# MCU_CAN.net
KiCad netlist of a schematic drawn in Altium Designer
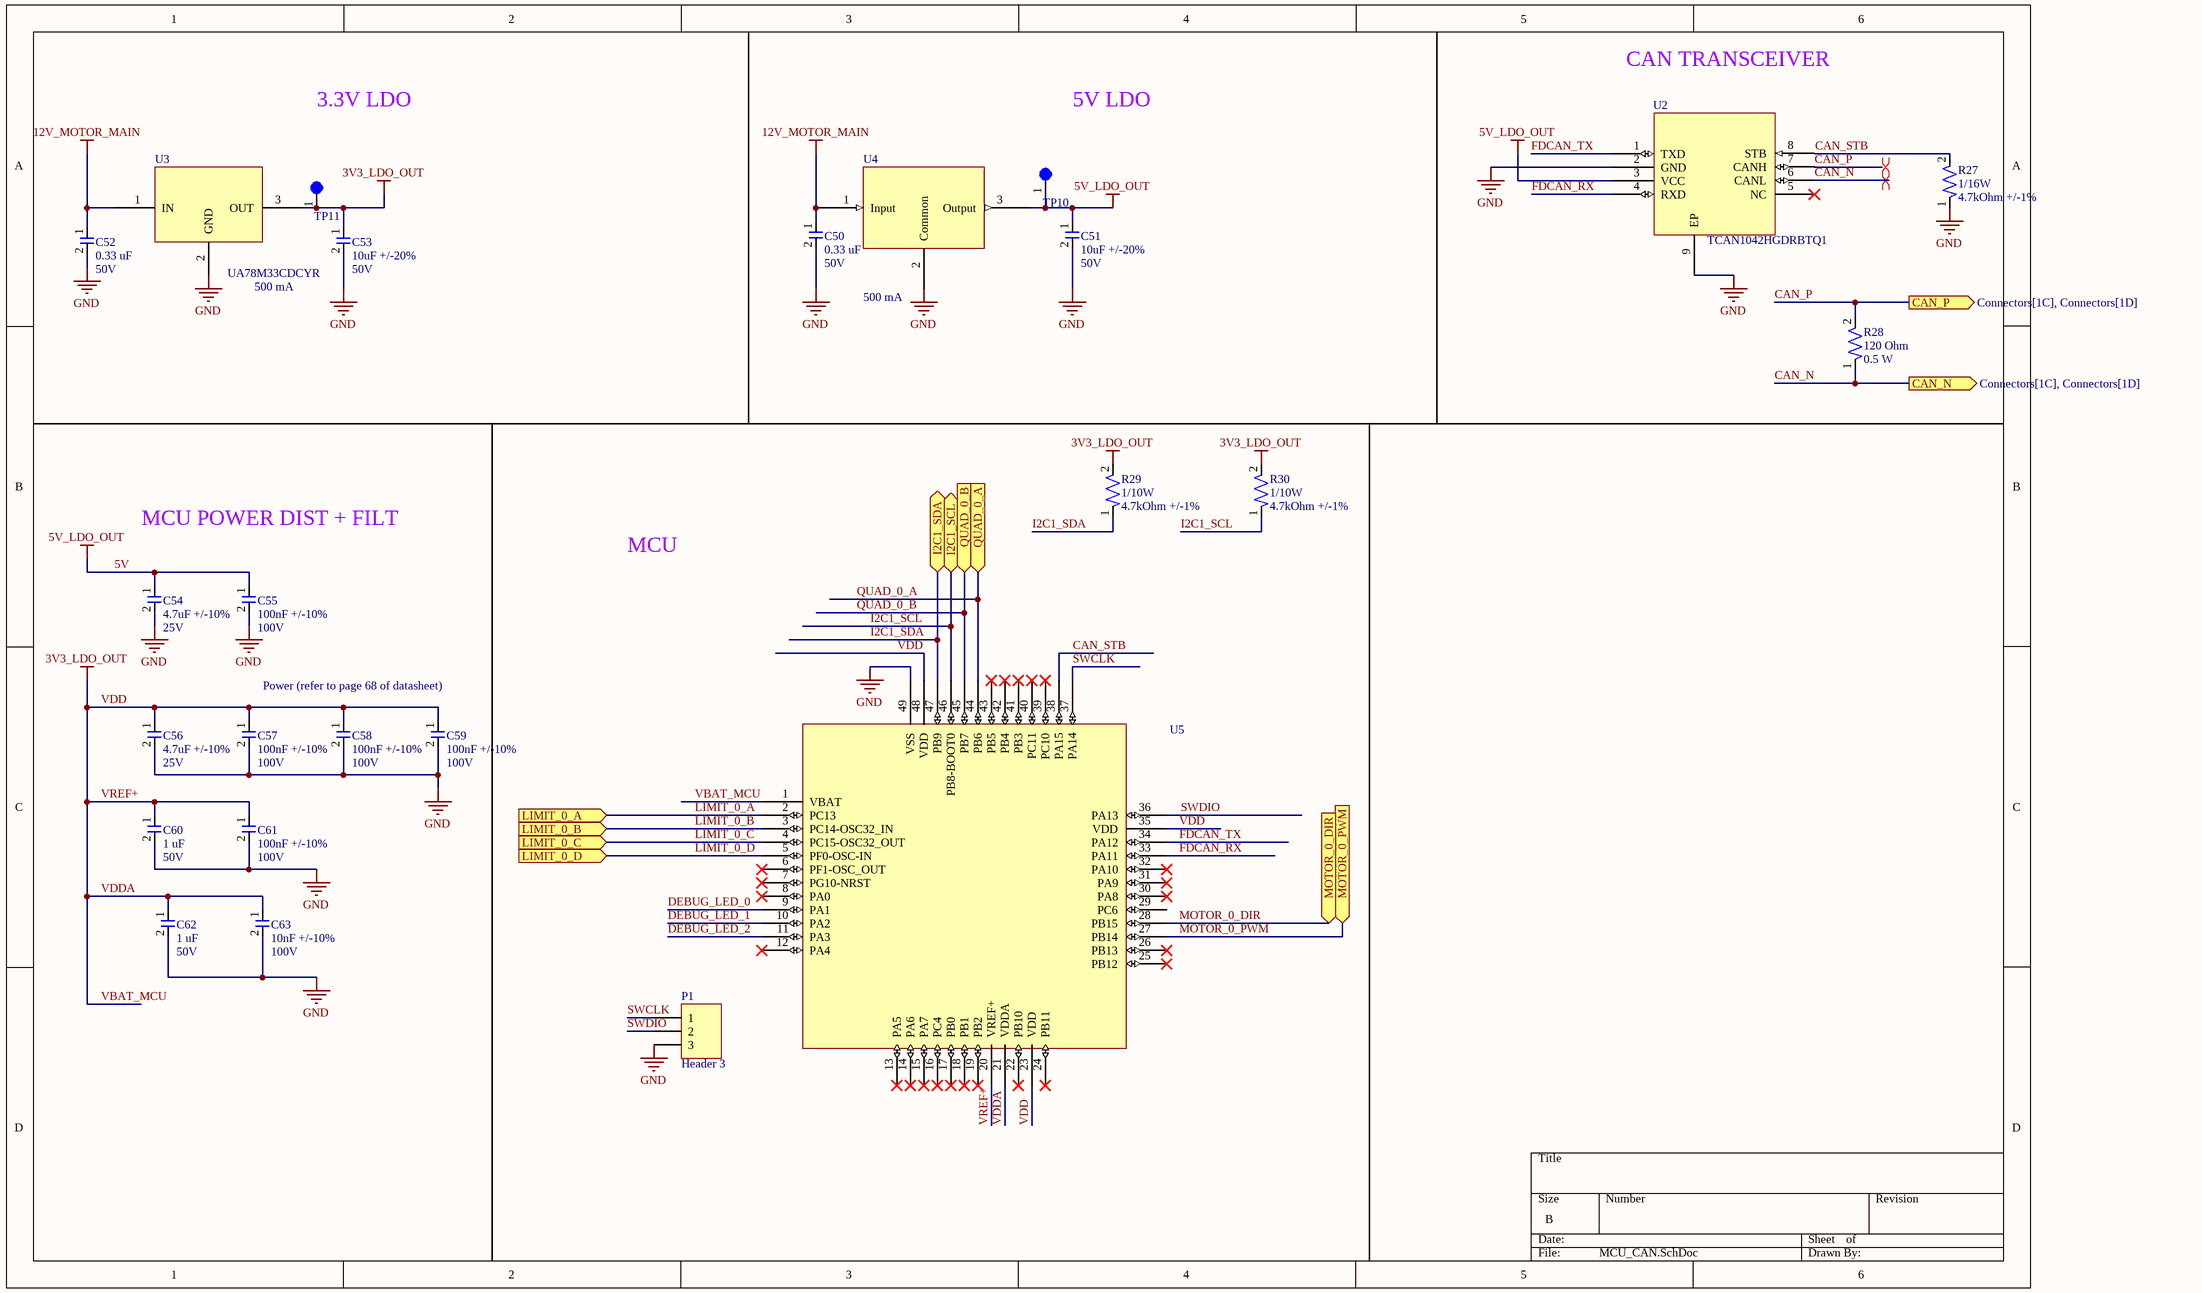
[diagram p0: MCU_CAN.SchDoc]

(export (version "E")
  (design (tool "Eeschema 10.0.6"))
  (components
    (comp (ref "C50")
      (value "CGA3E3X7R1H334K080AB")
      (footprint "CAP-0603")
      (description "0.33 µF ±10% 50V Ceramic Capacitor X7R 0603 (1608 Metric)")
      (fields
        (field (name "MANUFACTURER") "TDK Corporation")
        (field (name "TOLERANCE") "+/- 10%")
        (field (name "CAPACITANCE") "0.33 uF")
        (field (name "VOLTAGE") "50V")
      )
      (libsource (lib "MasterLib") (part "CAP-0.33uF-0001"))
    )
    (comp (ref "C51")
      (value "CL31B106KBHNNNE")
      (footprint "CAP-1206")
      (description "10 µF ±10% 50V Ceramic Capacitor X7R 1206 (3216 Metric)")
      (fields
        (field (name "MANUFACTURER") "Samsung Electro-Mechanics")
        (field (name "CAPACITANCE") "10uF +/-20%")
        (field (name "VOLTAGE RATING") "50V")
      )
      (libsource (lib "MasterLib") (part "CAP-10U-0001"))
    )
    (comp (ref "C52")
      (value "CGA3E3X7R1H334K080AB")
      (footprint "CAP-0603")
      (description "0.33 µF ±10% 50V Ceramic Capacitor X7R 0603 (1608 Metric)")
      (fields
        (field (name "MANUFACTURER") "TDK Corporation")
        (field (name "TOLERANCE") "+/- 10%")
        (field (name "CAPACITANCE") "0.33 uF")
        (field (name "VOLTAGE") "50V")
      )
      (libsource (lib "MasterLib") (part "CAP-0.33uF-0001"))
    )
    (comp (ref "C53")
      (value "CL31B106KBHNNNE")
      (footprint "CAP-1206")
      (description "10 µF ±10% 50V Ceramic Capacitor X7R 1206 (3216 Metric)")
      (fields
        (field (name "MANUFACTURER") "Samsung Electro-Mechanics")
        (field (name "CAPACITANCE") "10uF +/-20%")
        (field (name "VOLTAGE RATING") "50V")
      )
      (libsource (lib "MasterLib") (part "CAP-10U-0001"))
    )
    (comp (ref "C54")
      (value "TMK107BBJ475KA-T")
      (footprint "CAP-0603")
      (description "4.7 µF ±10% 25V Ceramic Capacitor X5R 0603 (1608 Metric)")
      (fields
        (field (name "MANUFACTURER") "Taiyo Yuden")
        (field (name "CAPACITANCE") "4.7uF +/-10%")
        (field (name "VOLTAGE RATING") "25V")
      )
      (libsource (lib "MasterLib") (part "CAP-4.7U-0001"))
    )
    (comp (ref "C55")
      (value "CC0603KRX7R0BB104")
      (footprint "CAP-0603")
      (description "CAP CER 0.1UF 100V X7R 0603")
      (fields
        (field (name "MANUFACTURER") "YAGEO")
        (field (name "CAPACITANCE") "100nF +/-10%")
        (field (name "VOLTAGE RATING") "100V")
      )
      (libsource (lib "MasterLib") (part "CAP-100N-0001"))
    )
    (comp (ref "C56")
      (value "TMK107BBJ475KA-T")
      (footprint "CAP-0603")
      (description "4.7 µF ±10% 25V Ceramic Capacitor X5R 0603 (1608 Metric)")
      (fields
        (field (name "MANUFACTURER") "Taiyo Yuden")
        (field (name "CAPACITANCE") "4.7uF +/-10%")
        (field (name "VOLTAGE RATING") "25V")
      )
      (libsource (lib "MasterLib") (part "CAP-4.7U-0001"))
    )
    (comp (ref "C57")
      (value "CC0603KRX7R0BB104")
      (footprint "CAP-0603")
      (description "CAP CER 0.1UF 100V X7R 0603")
      (fields
        (field (name "MANUFACTURER") "YAGEO")
        (field (name "CAPACITANCE") "100nF +/-10%")
        (field (name "VOLTAGE RATING") "100V")
      )
      (libsource (lib "MasterLib") (part "CAP-100N-0001"))
    )
    (comp (ref "C58")
      (value "CC0603KRX7R0BB104")
      (footprint "CAP-0603")
      (description "CAP CER 0.1UF 100V X7R 0603")
      (fields
        (field (name "MANUFACTURER") "YAGEO")
        (field (name "CAPACITANCE") "100nF +/-10%")
        (field (name "VOLTAGE RATING") "100V")
      )
      (libsource (lib "MasterLib") (part "CAP-100N-0001"))
    )
    (comp (ref "C59")
      (value "CC0603KRX7R0BB104")
      (footprint "CAP-0603")
      (description "CAP CER 0.1UF 100V X7R 0603")
      (fields
        (field (name "MANUFACTURER") "YAGEO")
        (field (name "CAPACITANCE") "100nF +/-10%")
        (field (name "VOLTAGE RATING") "100V")
      )
      (libsource (lib "MasterLib") (part "CAP-100N-0001"))
    )
    (comp (ref "C60")
      (value "UMK107AB7105KA-T")
      (footprint "CAP-0603")
      (description "1 µF ±10% 50V Ceramic Capacitor X7R 0603 (1608 Metric)")
      (fields (field (name "CAPACITANCE") "1 uF") (field (name "VOLTAGE") "50V"))
      (libsource (lib "MasterLib") (part "CAP-1U-0002"))
    )
    (comp (ref "C61")
      (value "CC0603KRX7R0BB104")
      (footprint "CAP-0603")
      (description "CAP CER 0.1UF 100V X7R 0603")
      (fields
        (field (name "MANUFACTURER") "YAGEO")
        (field (name "CAPACITANCE") "100nF +/-10%")
        (field (name "VOLTAGE RATING") "100V")
      )
      (libsource (lib "MasterLib") (part "CAP-100N-0001"))
    )
    (comp (ref "C62")
      (value "UMK107AB7105KA-T")
      (footprint "CAP-0603")
      (description "1 µF ±10% 50V Ceramic Capacitor X7R 0603 (1608 Metric)")
      (fields (field (name "CAPACITANCE") "1 uF") (field (name "VOLTAGE") "50V"))
      (libsource (lib "MasterLib") (part "CAP-1U-0002"))
    )
    (comp (ref "C63")
      (value "CC0402KRX7R0BB103")
      (footprint "CAP-0402")
      (description "10000 pF ±10% 100V Ceramic Capacitor X7R 0402 (1005 Metric)")
      (fields
        (field (name "MANUFACTURER") "YAGEO")
        (field (name "CAPACITANCE") "10nF +/-10%")
        (field (name "VOLTAGE RATING") "100V")
      )
      (libsource (lib "MasterLib") (part "CAP-10N-0001"))
    )
    (comp (ref "P1")
      (value "Header 3")
      (footprint "HDR1X3")
      (description "Header, 3-Pin")
      (fields (field (name "PUBLISHER") "Altium Limited"))
      (libsource (lib "Miscellaneous Connectors") (part "Header 3"))
    )
    (comp (ref "R27")
      (value "RC0402FR-074K7P")
      (footprint "RES-0402")
      (description "RES SMD 4.7K OHM 1% 1/16W 0402")
      (fields
        (field (name "MANUFACTURER") "YAGEO")
        (field (name "POWER RATING") "1/16W")
        (field (name "RESISTANCE") "4.7kOhm +/-1%")
      )
      (libsource (lib "MasterLib") (part "RES-4.7K-0001"))
    )
    (comp (ref "R28")
      (value "CRGH1206F120R")
      (footprint "RES-1206")
      (description "120 Ohms ±1% 0.5W, 1/2W Chip Resistor 1206 (3216 Metric) Thick Film")
      (fields
        (field (name "TOLERANCE") "1%")
        (field (name "RESISTANCE") "120 Ohm")
        (field (name "POWER") "0.5 W")
      )
      (libsource (lib "MasterLib") (part "RES-120-0002"))
    )
    (comp (ref "R29")
      (value "AF0603FR-074K7L")
      (footprint "RES-0603")
      (description "RES SMD 4.7K OHM 1% 1/10W 0603")
      (fields
        (field (name "MANUFACTURER") "YAGEO")
        (field (name "POWER RATING") "1/10W")
        (field (name "RESISTANCE") "4.7kOhm +/-1%")
      )
      (libsource (lib "MasterLib") (part "RES-4.7K-0002"))
    )
    (comp (ref "R30")
      (value "AF0603FR-074K7L")
      (footprint "RES-0603")
      (description "RES SMD 4.7K OHM 1% 1/10W 0603")
      (fields
        (field (name "MANUFACTURER") "YAGEO")
        (field (name "POWER RATING") "1/10W")
        (field (name "RESISTANCE") "4.7kOhm +/-1%")
      )
      (libsource (lib "MasterLib") (part "RES-4.7K-0002"))
    )
    (comp (ref "TP10")
      (value "5003")
      (footprint "TEST-POINT-0001")
      (description "Oranange PC Test Point, Miniature Phoisphor Bronze Silver Plating Through Hole Mounting Type")
      (libsource (lib "MasterLib") (part "TEST-POINT-0001"))
    )
    (comp (ref "TP11")
      (value "5003")
      (footprint "TEST-POINT-0001")
      (description "Oranange PC Test Point, Miniature Phoisphor Bronze Silver Plating Through Hole Mounting Type")
      (libsource (lib "MasterLib") (part "TEST-POINT-0001"))
    )
    (comp (ref "U2")
      (value "TCAN1042HGDRBTQ1")
      (footprint "IC-8-VSON")
      (description "1/1 Transceiver CANbus 8-VSON (3x3)")
      (fields (field (name "MANUFACTURER") "Texas Instrument"))
      (libsource (lib "MasterLib") (part "IC-CAN-TRANSCEIVER-0002"))
    )
    (comp (ref "U3")
      (value "UA78M33CDCYR")
      (footprint "IC-SOT-223-4")
      (description "Linear Voltage Regulator IC Positive Fixed 1 Output 500mA SOT-223-4")
      (fields (field (name "CURRENT") "500 mA"))
      (libsource (lib "MasterLib") (part "IC-LDO-3.3V-0002"))
    )
    (comp (ref "U4")
      (value "UA78M05IDCYR")
      (footprint "IC-SOT-223-4")
      (description "Linear Voltage Regulator IC Positive Fixed 1 Output 500mA SOT-223-4")
      (fields (field (name "MANUFACTURER") "Texas Instruments") (field (name "CURRENT") "500 mA"))
      (libsource (lib "MasterLib") (part "IC-LDO-5V-0003"))
    )
    (comp (ref "U5")
      (value "STM32G431CBU6")
      (footprint "MCU-UFQFPN48")
      (libsource (lib "MasterLib") (part "IC-STM32G431CBU6"))
    )
  )
  (nets
    (net (code "1") (name "/CAN_N") (class "Default")
      (node (ref "R28") (pin "1") (pinfunction "1_1") (pintype "passive"))
      (node (ref "U2") (pin "6") (pinfunction "CANL_6") (pintype "bidirectional"))
    )
    (net (code "2") (name "/CAN_P") (class "Default")
      (node (ref "R28") (pin "2") (pinfunction "2_2") (pintype "passive"))
      (node (ref "U2") (pin "7") (pinfunction "CANH_7") (pintype "bidirectional"))
    )
    (net (code "3") (name "/CAN_STB") (class "Default")
      (node (ref "R27") (pin "2") (pinfunction "2_2") (pintype "passive"))
      (node (ref "U2") (pin "8") (pinfunction "STB_8") (pintype "input"))
      (node (ref "U5") (pin "38") (pinfunction "PA15_38") (pintype "bidirectional"))
    )
    (net (code "4") (name "/DEBUG_LED_0") (class "Default")
      (node (ref "U5") (pin "9") (pinfunction "PA1_9") (pintype "bidirectional"))
    )
    (net (code "5") (name "/DEBUG_LED_1") (class "Default")
      (node (ref "U5") (pin "10") (pinfunction "PA2_10") (pintype "bidirectional"))
    )
    (net (code "6") (name "/DEBUG_LED_2") (class "Default")
      (node (ref "U5") (pin "11") (pinfunction "PA3_11") (pintype "bidirectional"))
    )
    (net (code "7") (name "/FDCAN_RX") (class "Default")
      (node (ref "U2") (pin "4") (pinfunction "RXD_4") (pintype "bidirectional"))
      (node (ref "U5") (pin "33") (pinfunction "PA11_33") (pintype "bidirectional"))
    )
    (net (code "8") (name "/FDCAN_TX") (class "Default")
      (node (ref "U2") (pin "1") (pinfunction "TXD_1") (pintype "bidirectional"))
      (node (ref "U5") (pin "34") (pinfunction "PA12_34") (pintype "bidirectional"))
    )
    (net (code "9") (name "/I2C1_SCL") (class "Default")
      (node (ref "R30") (pin "1") (pinfunction "1_1") (pintype "passive"))
      (node (ref "U5") (pin "46") (pinfunction "PB8-BOOT0_46") (pintype "bidirectional"))
    )
    (net (code "10") (name "/I2C1_SDA") (class "Default")
      (node (ref "R29") (pin "1") (pinfunction "1_1") (pintype "passive"))
      (node (ref "U5") (pin "47") (pinfunction "PB9_47") (pintype "bidirectional"))
    )
    (net (code "11") (name "/LIMIT_0_A") (class "Default")
      (node (ref "U5") (pin "2") (pinfunction "PC13_2") (pintype "bidirectional"))
    )
    (net (code "12") (name "/LIMIT_0_B") (class "Default")
      (node (ref "U5") (pin "3") (pinfunction "PC14-OSC32_IN_3") (pintype "bidirectional"))
    )
    (net (code "13") (name "/LIMIT_0_C") (class "Default")
      (node (ref "U5") (pin "4") (pinfunction "PC15-OSC32_OUT_4") (pintype "bidirectional"))
    )
    (net (code "14") (name "/LIMIT_0_D") (class "Default")
      (node (ref "U5") (pin "5") (pinfunction "PF0-OSC-IN_5") (pintype "bidirectional"))
    )
    (net (code "15") (name "/MOTOR_0_DIR") (class "Default")
      (node (ref "U5") (pin "28") (pinfunction "PB15_28") (pintype "bidirectional"))
    )
    (net (code "16") (name "/MOTOR_0_PWM") (class "Default")
      (node (ref "U5") (pin "27") (pinfunction "PB14_27") (pintype "bidirectional"))
    )
    (net (code "17") (name "/QUAD_0_A") (class "Default")
      (node (ref "U5") (pin "44") (pinfunction "PB6_44") (pintype "bidirectional"))
    )
    (net (code "18") (name "/QUAD_0_B") (class "Default")
      (node (ref "U5") (pin "45") (pinfunction "PB7_45") (pintype "bidirectional"))
    )
    (net (code "19") (name "/SWCLK") (class "Default")
      (node (ref "P1") (pin "1") (pinfunction "1_1") (pintype "passive"))
      (node (ref "U5") (pin "37") (pinfunction "PA14_37") (pintype "bidirectional"))
    )
    (net (code "20") (name "/SWDIO") (class "Default")
      (node (ref "P1") (pin "2") (pinfunction "2_2") (pintype "passive"))
      (node (ref "U5") (pin "36") (pinfunction "PA13_36") (pintype "bidirectional"))
    )
    (net (code "21") (name "3V3_LDO_OUT") (class "Default")
      (node (ref "C53") (pin "1") (pinfunction "1_1") (pintype "passive"))
      (node (ref "C56") (pin "1") (pinfunction "1_1") (pintype "passive"))
      (node (ref "C57") (pin "1") (pinfunction "1_1") (pintype "passive"))
      (node (ref "C58") (pin "1") (pinfunction "1_1") (pintype "passive"))
      (node (ref "C59") (pin "1") (pinfunction "1_1") (pintype "passive"))
      (node (ref "C60") (pin "1") (pinfunction "1_1") (pintype "passive"))
      (node (ref "C61") (pin "1") (pinfunction "1_1") (pintype "passive"))
      (node (ref "C62") (pin "1") (pinfunction "1_1") (pintype "passive"))
      (node (ref "C63") (pin "1") (pinfunction "1_1") (pintype "passive"))
      (node (ref "R29") (pin "2") (pinfunction "2_2") (pintype "passive"))
      (node (ref "R30") (pin "2") (pinfunction "2_2") (pintype "passive"))
      (node (ref "TP11") (pin "1") (pinfunction "0_1") (pintype "passive"))
      (node (ref "U3") (pin "3") (pinfunction "OUT_3") (pintype "power_in"))
      (node (ref "U5") (pin "1") (pinfunction "VBAT_1") (pintype "power_in"))
      (node (ref "U5") (pin "20") (pinfunction "VREF+_20") (pintype "power_in"))
      (node (ref "U5") (pin "21") (pinfunction "VDDA_21") (pintype "power_in"))
      (node (ref "U5") (pin "23") (pinfunction "VDD_23") (pintype "power_in"))
      (node (ref "U5") (pin "35") (pinfunction "VDD_35") (pintype "power_in"))
      (node (ref "U5") (pin "48") (pinfunction "VDD_48") (pintype "power_in"))
    )
    (net (code "22") (name "5V_LDO_OUT") (class "Default")
      (node (ref "C51") (pin "1") (pinfunction "1_1") (pintype "passive"))
      (node (ref "C54") (pin "1") (pinfunction "1_1") (pintype "passive"))
      (node (ref "C55") (pin "1") (pinfunction "1_1") (pintype "passive"))
      (node (ref "TP10") (pin "1") (pinfunction "0_1") (pintype "passive"))
      (node (ref "U2") (pin "3") (pinfunction "VCC_3") (pintype "power_in"))
      (node (ref "U4") (pin "3") (pinfunction "Output_3") (pintype "output"))
    )
    (net (code "23") (name "12V_MOTOR_MAIN") (class "Default")
      (node (ref "C50") (pin "1") (pinfunction "1_1") (pintype "passive"))
      (node (ref "C52") (pin "1") (pinfunction "1_1") (pintype "passive"))
      (node (ref "U3") (pin "1") (pinfunction "IN_1") (pintype "power_in"))
      (node (ref "U4") (pin "1") (pinfunction "Input_1") (pintype "input"))
    )
    (net (code "24") (name "GND") (class "Default")
      (node (ref "C50") (pin "2") (pinfunction "2_2") (pintype "passive"))
      (node (ref "C51") (pin "2") (pinfunction "2_2") (pintype "passive"))
      (node (ref "C52") (pin "2") (pinfunction "2_2") (pintype "passive"))
      (node (ref "C53") (pin "2") (pinfunction "2_2") (pintype "passive"))
      (node (ref "C54") (pin "2") (pinfunction "2_2") (pintype "passive"))
      (node (ref "C55") (pin "2") (pinfunction "2_2") (pintype "passive"))
      (node (ref "C56") (pin "2") (pinfunction "2_2") (pintype "passive"))
      (node (ref "C57") (pin "2") (pinfunction "2_2") (pintype "passive"))
      (node (ref "C58") (pin "2") (pinfunction "2_2") (pintype "passive"))
      (node (ref "C59") (pin "2") (pinfunction "2_2") (pintype "passive"))
      (node (ref "C60") (pin "2") (pinfunction "2_2") (pintype "passive"))
      (node (ref "C61") (pin "2") (pinfunction "2_2") (pintype "passive"))
      (node (ref "C62") (pin "2") (pinfunction "2_2") (pintype "passive"))
      (node (ref "C63") (pin "2") (pinfunction "2_2") (pintype "passive"))
      (node (ref "P1") (pin "3") (pinfunction "3_3") (pintype "passive"))
      (node (ref "R27") (pin "1") (pinfunction "1_1") (pintype "passive"))
      (node (ref "U2") (pin "2") (pinfunction "GND_2") (pintype "power_in"))
      (node (ref "U2") (pin "9") (pinfunction "EP_9") (pintype "power_in"))
      (node (ref "U3") (pin "2") (pinfunction "GND_2") (pintype "power_in"))
      (node (ref "U4") (pin "2") (pinfunction "Common_2") (pintype "power_in"))
      (node (ref "U5") (pin "49") (pinfunction "VSS_49") (pintype "power_in"))
    )
    (net (code "25") (name "unconnected-(U2-NC-Pad5)") (class "Default")
      (node (ref "U2") (pin "5") (pinfunction "NC_5") (pintype "power_in+no_connect"))
    )
    (net (code "26") (name "unconnected-(U5-PA0-Pad8)") (class "Default")
      (node (ref "U5") (pin "8") (pinfunction "PA0_8") (pintype "bidirectional+no_connect"))
    )
    (net (code "27") (name "unconnected-(U5-PA4-Pad12)") (class "Default")
      (node (ref "U5") (pin "12") (pinfunction "PA4_12") (pintype "bidirectional+no_connect"))
    )
    (net (code "28") (name "unconnected-(U5-PA5-Pad13)") (class "Default")
      (node (ref "U5") (pin "13") (pinfunction "PA5_13") (pintype "bidirectional+no_connect"))
    )
    (net (code "29") (name "unconnected-(U5-PA6-Pad14)") (class "Default")
      (node (ref "U5") (pin "14") (pinfunction "PA6_14") (pintype "bidirectional+no_connect"))
    )
    (net (code "30") (name "unconnected-(U5-PA7-Pad15)") (class "Default")
      (node (ref "U5") (pin "15") (pinfunction "PA7_15") (pintype "bidirectional+no_connect"))
    )
    (net (code "31") (name "unconnected-(U5-PA8-Pad30)") (class "Default")
      (node (ref "U5") (pin "30") (pinfunction "PA8_30") (pintype "bidirectional+no_connect"))
    )
    (net (code "32") (name "unconnected-(U5-PA9-Pad31)") (class "Default")
      (node (ref "U5") (pin "31") (pinfunction "PA9_31") (pintype "bidirectional+no_connect"))
    )
    (net (code "33") (name "unconnected-(U5-PA10-Pad32)") (class "Default")
      (node (ref "U5") (pin "32") (pinfunction "PA10_32") (pintype "bidirectional+no_connect"))
    )
    (net (code "34") (name "unconnected-(U5-PB0-Pad17)") (class "Default")
      (node (ref "U5") (pin "17") (pinfunction "PB0_17") (pintype "bidirectional+no_connect"))
    )
    (net (code "35") (name "unconnected-(U5-PB1-Pad18)") (class "Default")
      (node (ref "U5") (pin "18") (pinfunction "PB1_18") (pintype "bidirectional+no_connect"))
    )
    (net (code "36") (name "unconnected-(U5-PB2-Pad19)") (class "Default")
      (node (ref "U5") (pin "19") (pinfunction "PB2_19") (pintype "bidirectional+no_connect"))
    )
    (net (code "37") (name "unconnected-(U5-PB3-Pad41)") (class "Default")
      (node (ref "U5") (pin "41") (pinfunction "PB3_41") (pintype "bidirectional+no_connect"))
    )
    (net (code "38") (name "unconnected-(U5-PB4-Pad42)") (class "Default")
      (node (ref "U5") (pin "42") (pinfunction "PB4_42") (pintype "bidirectional+no_connect"))
    )
    (net (code "39") (name "unconnected-(U5-PB5-Pad43)") (class "Default")
      (node (ref "U5") (pin "43") (pinfunction "PB5_43") (pintype "bidirectional+no_connect"))
    )
    (net (code "40") (name "unconnected-(U5-PB10-Pad22)") (class "Default")
      (node (ref "U5") (pin "22") (pinfunction "PB10_22") (pintype "bidirectional+no_connect"))
    )
    (net (code "41") (name "unconnected-(U5-PB11-Pad24)") (class "Default")
      (node (ref "U5") (pin "24") (pinfunction "PB11_24") (pintype "bidirectional+no_connect"))
    )
    (net (code "42") (name "unconnected-(U5-PB12-Pad25)") (class "Default")
      (node (ref "U5") (pin "25") (pinfunction "PB12_25") (pintype "bidirectional+no_connect"))
    )
    (net (code "43") (name "unconnected-(U5-PB13-Pad26)") (class "Default")
      (node (ref "U5") (pin "26") (pinfunction "PB13_26") (pintype "bidirectional+no_connect"))
    )
    (net (code "44") (name "unconnected-(U5-PC4-Pad16)") (class "Default")
      (node (ref "U5") (pin "16") (pinfunction "PC4_16") (pintype "bidirectional+no_connect"))
    )
    (net (code "45") (name "unconnected-(U5-PC6-Pad29)") (class "Default")
      (node (ref "U5") (pin "29") (pinfunction "PC6_29") (pintype "bidirectional"))
    )
    (net (code "46") (name "unconnected-(U5-PC10-Pad39)") (class "Default")
      (node (ref "U5") (pin "39") (pinfunction "PC10_39") (pintype "bidirectional+no_connect"))
    )
    (net (code "47") (name "unconnected-(U5-PC11-Pad40)") (class "Default")
      (node (ref "U5") (pin "40") (pinfunction "PC11_40") (pintype "bidirectional+no_connect"))
    )
    (net (code "48") (name "unconnected-(U5-PF1-OSC_OUT-Pad6)") (class "Default")
      (node (ref "U5") (pin "6") (pinfunction "PF1-OSC_OUT_6") (pintype "bidirectional+no_connect"))
    )
    (net (code "49") (name "unconnected-(U5-PG10-NRST-Pad7)") (class "Default")
      (node (ref "U5") (pin "7") (pinfunction "PG10-NRST_7") (pintype "bidirectional+no_connect"))
    )
  )
)
